# deflection_amplifier.net
KiCad netlist of a schematic drawn in EAGLE
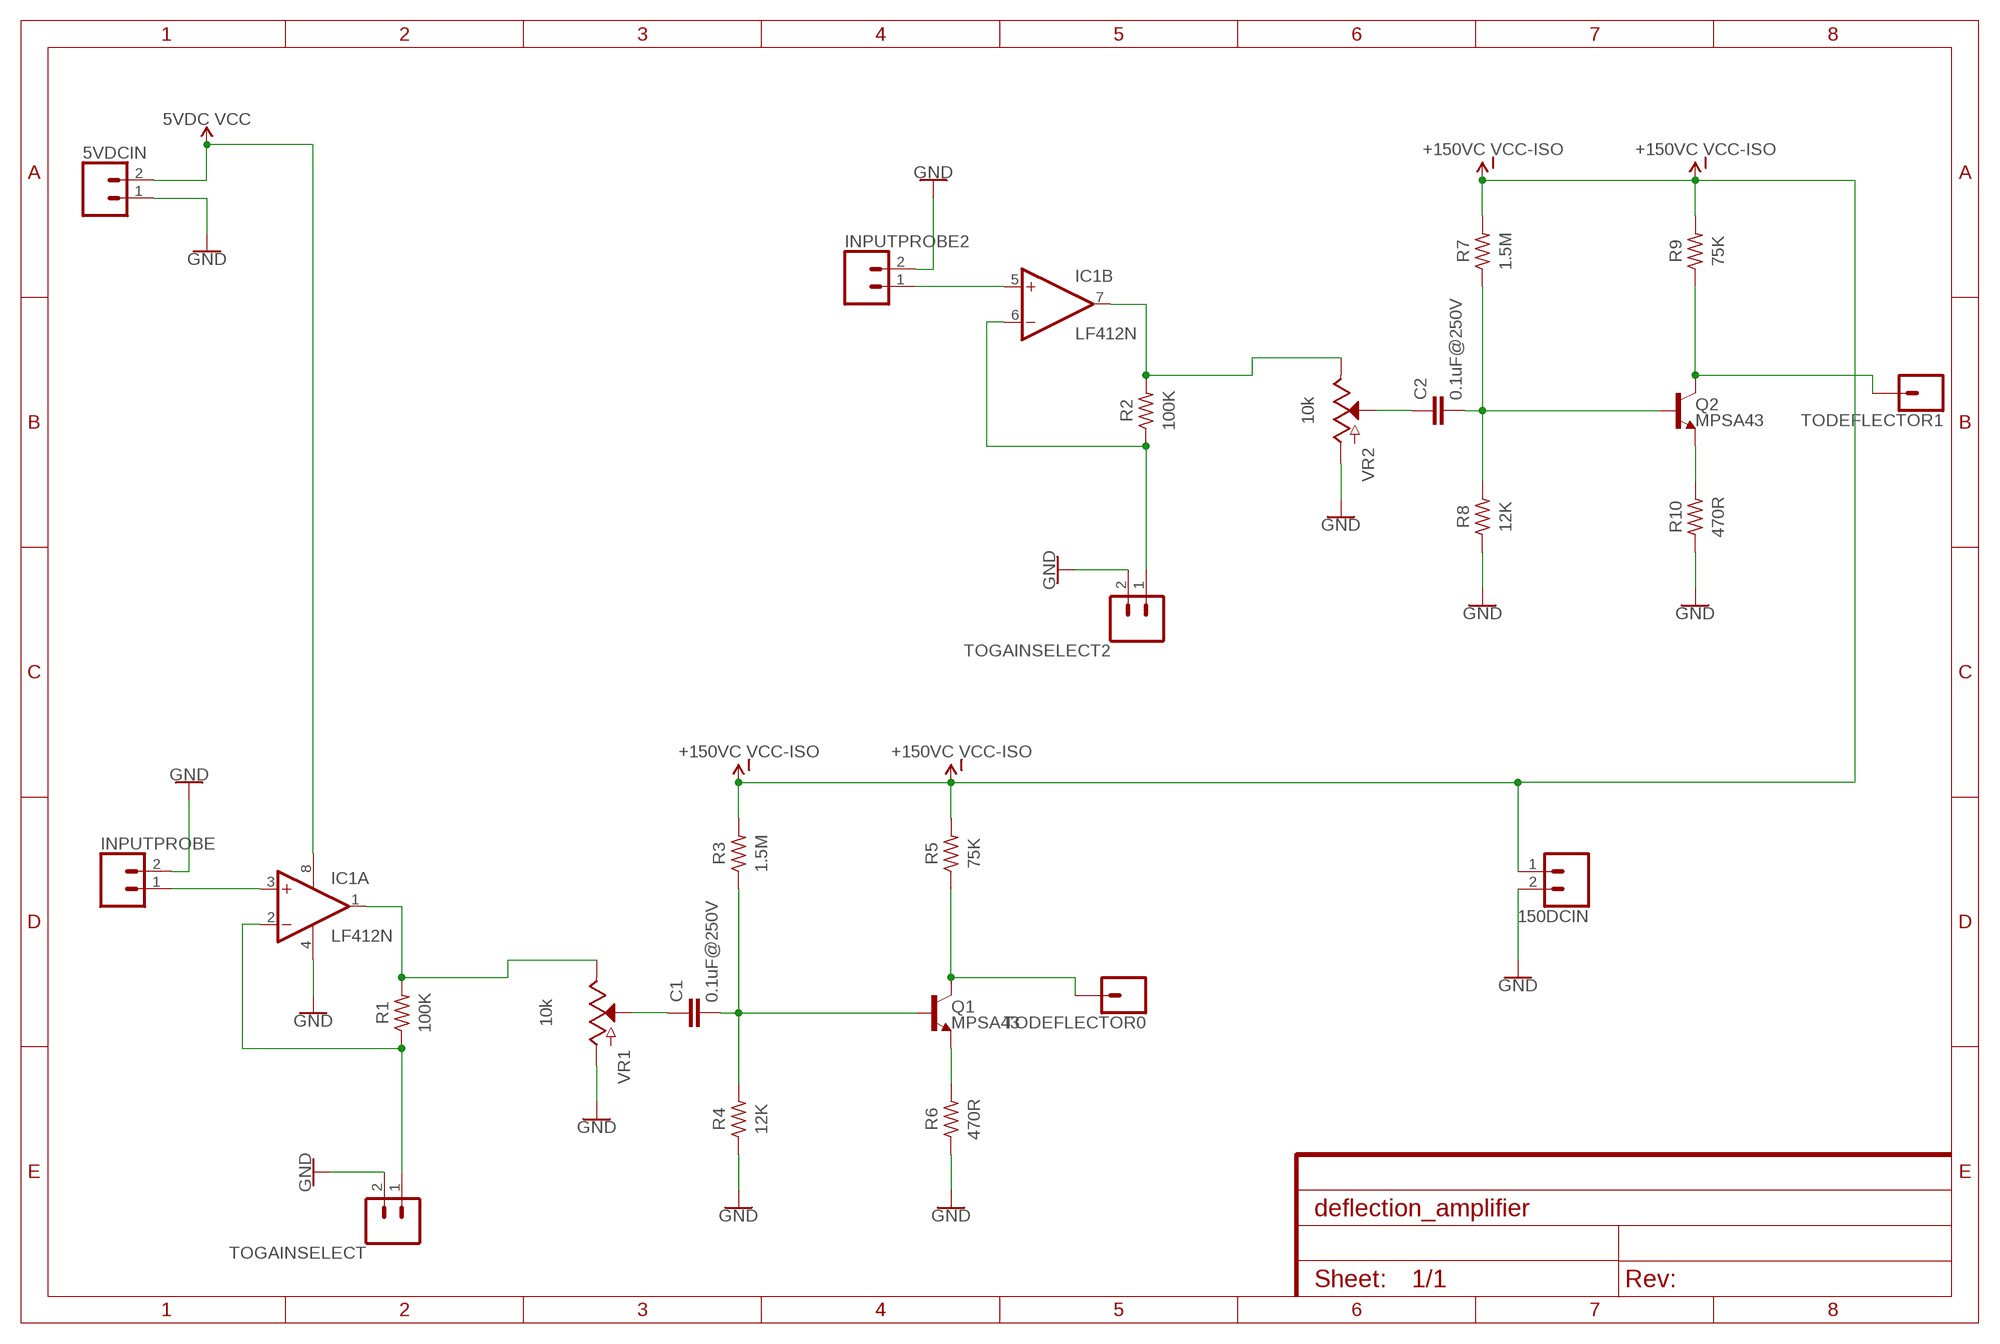
[diagram p0: schematic, sheet 1]

(export (version "E")
  (design (tool "Eeschema 10.0.6"))
  (components
    (comp (ref "5VDCIN")
      (value "CONN_02")
      (footprint "eagle-import:1X02")
      (libsource (lib "eagle-import") (part "CONN_02"))
    )
    (comp (ref "150DCIN")
      (value "CONN_02")
      (footprint "eagle-import:1X02")
      (libsource (lib "eagle-import") (part "CONN_02"))
    )
    (comp (ref "C1")
      (value "0.1uF@250V")
      (footprint "eagle-import:C15B8")
      (libsource (lib "eagle-import") (part "C15/8"))
    )
    (comp (ref "C2")
      (value "0.1uF@250V")
      (footprint "eagle-import:C15B8")
      (libsource (lib "eagle-import") (part "C15/8"))
    )
    (comp (ref "IC1")
      (value "LF412N")
      (footprint "eagle-import:DIL08")
      (libsource (lib "eagle-import") (part "LF412N"))
    )
    (comp (ref "INPUTPROBE")
      (value "CONN_02")
      (footprint "eagle-import:1X02")
      (libsource (lib "eagle-import") (part "CONN_02"))
    )
    (comp (ref "INPUTPROBE2")
      (value "CONN_02")
      (footprint "eagle-import:1X02")
      (libsource (lib "eagle-import") (part "CONN_02"))
    )
    (comp (ref "Q1")
      (value "MPSA43")
      (footprint "eagle-import:TO-92")
      (libsource (lib "eagle-import") (part "TRANS_NPN-2N3904"))
    )
    (comp (ref "Q2")
      (value "MPSA43")
      (footprint "eagle-import:TO-92")
      (libsource (lib "eagle-import") (part "TRANS_NPN-2N3904"))
    )
    (comp (ref "R1")
      (value "100K")
      (footprint "eagle-import:RESAD1176W63L850D250B")
      (libsource (lib "eagle-import") (part "R-USAXIAL-11.7MM-PITCH_"))
    )
    (comp (ref "R2")
      (value "100K")
      (footprint "eagle-import:RESAD1176W63L850D250B")
      (libsource (lib "eagle-import") (part "R-USAXIAL-11.7MM-PITCH_"))
    )
    (comp (ref "R3")
      (value "1.5M")
      (footprint "eagle-import:RESAD1176W63L850D250B")
      (libsource (lib "eagle-import") (part "R-USAXIAL-11.7MM-PITCH_"))
    )
    (comp (ref "R4")
      (value "12K")
      (footprint "eagle-import:RESAD1176W63L850D250B")
      (libsource (lib "eagle-import") (part "R-USAXIAL-11.7MM-PITCH_"))
    )
    (comp (ref "R5")
      (value "75K")
      (footprint "eagle-import:RESAD1176W63L850D250B")
      (libsource (lib "eagle-import") (part "R-USAXIAL-11.7MM-PITCH_"))
    )
    (comp (ref "R6")
      (value "470R")
      (footprint "eagle-import:RESAD1176W63L850D250B")
      (libsource (lib "eagle-import") (part "R-USAXIAL-11.7MM-PITCH_"))
    )
    (comp (ref "R7")
      (value "1.5M")
      (footprint "eagle-import:RESAD1176W63L850D250B")
      (libsource (lib "eagle-import") (part "R-USAXIAL-11.7MM-PITCH_"))
    )
    (comp (ref "R8")
      (value "12K")
      (footprint "eagle-import:RESAD1176W63L850D250B")
      (libsource (lib "eagle-import") (part "R-USAXIAL-11.7MM-PITCH_"))
    )
    (comp (ref "R9")
      (value "75K")
      (footprint "eagle-import:RESAD1176W63L850D250B")
      (libsource (lib "eagle-import") (part "R-USAXIAL-11.7MM-PITCH_"))
    )
    (comp (ref "R10")
      (value "470R")
      (footprint "eagle-import:RESAD1176W63L850D250B")
      (libsource (lib "eagle-import") (part "R-USAXIAL-11.7MM-PITCH_"))
    )
    (comp (ref "TODEFLECTOR0")
      (value "CONN_01")
      (footprint "eagle-import:1X01")
      (libsource (lib "eagle-import") (part "CONN_01"))
    )
    (comp (ref "TODEFLECTOR1")
      (value "CONN_01")
      (footprint "eagle-import:1X01")
      (libsource (lib "eagle-import") (part "CONN_01"))
    )
    (comp (ref "TOGAINSELECT")
      (value "CONN_02")
      (footprint "eagle-import:1X02")
      (libsource (lib "eagle-import") (part "CONN_02"))
    )
    (comp (ref "TOGAINSELECT2")
      (value "CONN_02")
      (footprint "eagle-import:1X02")
      (libsource (lib "eagle-import") (part "CONN_02"))
    )
    (comp (ref "VR1")
      (value "10k")
      (footprint "eagle-import:POT-PTH-ALPS")
      (libsource (lib "eagle-import") (part "POTENTIOMETER-PTH-9MM-1/20W-20%"))
    )
    (comp (ref "VR2")
      (value "10k")
      (footprint "eagle-import:POT-PTH-ALPS")
      (libsource (lib "eagle-import") (part "POTENTIOMETER-PTH-9MM-1/20W-20%"))
    )
  )
  (nets
    (net (code "1") (name "+150VC VCC-ISO") (class "Default")
      (node (ref "150DCIN") (pin "1") (pinfunction "1_1") (pintype "passive"))
      (node (ref "R3") (pin "2") (pinfunction "2_2") (pintype "passive"))
      (node (ref "R5") (pin "2") (pinfunction "2_2") (pintype "passive"))
      (node (ref "R7") (pin "2") (pinfunction "2_2") (pintype "passive"))
      (node (ref "R9") (pin "2") (pinfunction "2_2") (pintype "passive"))
    )
    (net (code "2") (name "5VDC VCC") (class "Default")
      (node (ref "5VDCIN") (pin "2") (pinfunction "2_2") (pintype "passive"))
      (node (ref "IC1") (pin "8") (pinfunction "V+_8") (pintype "power_in"))
    )
    (net (code "3") (name "GND") (class "Default")
      (node (ref "150DCIN") (pin "2") (pinfunction "2_2") (pintype "passive"))
      (node (ref "5VDCIN") (pin "1") (pinfunction "1_1") (pintype "passive"))
      (node (ref "IC1") (pin "4") (pinfunction "V-_4") (pintype "power_in"))
      (node (ref "INPUTPROBE") (pin "2") (pinfunction "2_2") (pintype "passive"))
      (node (ref "INPUTPROBE2") (pin "2") (pinfunction "2_2") (pintype "passive"))
      (node (ref "R10") (pin "1") (pinfunction "1_1") (pintype "passive"))
      (node (ref "R4") (pin "1") (pinfunction "1_1") (pintype "passive"))
      (node (ref "R6") (pin "1") (pinfunction "1_1") (pintype "passive"))
      (node (ref "R8") (pin "1") (pinfunction "1_1") (pintype "passive"))
      (node (ref "TOGAINSELECT") (pin "2") (pinfunction "2_2") (pintype "passive"))
      (node (ref "TOGAINSELECT2") (pin "2") (pinfunction "2_2") (pintype "passive"))
      (node (ref "VR1") (pin "P$3") (pinfunction "A_P$3") (pintype "passive"))
      (node (ref "VR2") (pin "P$3") (pinfunction "A_P$3") (pintype "passive"))
    )
    (net (code "4") (name "Net-(IC1A-+IN)") (class "Default")
      (node (ref "IC1") (pin "3") (pinfunction "+IN_3") (pintype "input"))
      (node (ref "INPUTPROBE") (pin "1") (pinfunction "1_1") (pintype "passive"))
    )
    (net (code "5") (name "Net-(IC1A--IN)") (class "Default")
      (node (ref "IC1") (pin "2") (pinfunction "-IN_2") (pintype "input"))
      (node (ref "R1") (pin "1") (pinfunction "1_1") (pintype "passive"))
      (node (ref "TOGAINSELECT") (pin "1") (pinfunction "1_1") (pintype "passive"))
    )
    (net (code "6") (name "Net-(IC1A-OUT)") (class "Default")
      (node (ref "IC1") (pin "1") (pinfunction "OUT_1") (pintype "output"))
      (node (ref "R1") (pin "2") (pinfunction "2_2") (pintype "passive"))
      (node (ref "VR1") (pin "P$1") (pinfunction "E_P$1") (pintype "passive"))
    )
    (net (code "7") (name "Net-(IC1B-+IN)") (class "Default")
      (node (ref "IC1") (pin "5") (pinfunction "+IN_5") (pintype "input"))
      (node (ref "INPUTPROBE2") (pin "1") (pinfunction "1_1") (pintype "passive"))
    )
    (net (code "8") (name "Net-(IC1B--IN)") (class "Default")
      (node (ref "IC1") (pin "6") (pinfunction "-IN_6") (pintype "input"))
      (node (ref "R2") (pin "1") (pinfunction "1_1") (pintype "passive"))
      (node (ref "TOGAINSELECT2") (pin "1") (pinfunction "1_1") (pintype "passive"))
    )
    (net (code "9") (name "Net-(IC1B-OUT)") (class "Default")
      (node (ref "IC1") (pin "7") (pinfunction "OUT_7") (pintype "output"))
      (node (ref "R2") (pin "2") (pinfunction "2_2") (pintype "passive"))
      (node (ref "VR2") (pin "P$1") (pinfunction "E_P$1") (pintype "passive"))
    )
    (net (code "10") (name "Net-(Q1-B)") (class "Default")
      (node (ref "C1") (pin "2") (pinfunction "2_2") (pintype "passive"))
      (node (ref "Q1") (pin "2") (pinfunction "B_2") (pintype "passive"))
      (node (ref "R3") (pin "1") (pinfunction "1_1") (pintype "passive"))
      (node (ref "R4") (pin "2") (pinfunction "2_2") (pintype "passive"))
    )
    (net (code "11") (name "Net-(Q1-C)") (class "Default")
      (node (ref "Q1") (pin "3") (pinfunction "C_3") (pintype "passive"))
      (node (ref "R5") (pin "1") (pinfunction "1_1") (pintype "passive"))
      (node (ref "TODEFLECTOR0") (pin "1") (pinfunction "1_1") (pintype "passive"))
    )
    (net (code "12") (name "Net-(Q1-E)") (class "Default")
      (node (ref "Q1") (pin "1") (pinfunction "E_1") (pintype "passive"))
      (node (ref "R6") (pin "2") (pinfunction "2_2") (pintype "passive"))
    )
    (net (code "13") (name "Net-(Q2-B)") (class "Default")
      (node (ref "C2") (pin "2") (pinfunction "2_2") (pintype "passive"))
      (node (ref "Q2") (pin "2") (pinfunction "B_2") (pintype "passive"))
      (node (ref "R7") (pin "1") (pinfunction "1_1") (pintype "passive"))
      (node (ref "R8") (pin "2") (pinfunction "2_2") (pintype "passive"))
    )
    (net (code "14") (name "Net-(Q2-C)") (class "Default")
      (node (ref "Q2") (pin "3") (pinfunction "C_3") (pintype "passive"))
      (node (ref "R9") (pin "1") (pinfunction "1_1") (pintype "passive"))
      (node (ref "TODEFLECTOR1") (pin "1") (pinfunction "1_1") (pintype "passive"))
    )
    (net (code "15") (name "Net-(Q2-E)") (class "Default")
      (node (ref "Q2") (pin "1") (pinfunction "E_1") (pintype "passive"))
      (node (ref "R10") (pin "2") (pinfunction "2_2") (pintype "passive"))
    )
    (net (code "16") (name "Net-(VR1-S)") (class "Default")
      (node (ref "C1") (pin "1") (pinfunction "1_1") (pintype "passive"))
      (node (ref "VR1") (pin "P$2") (pinfunction "S_P$2") (pintype "passive"))
    )
    (net (code "17") (name "Net-(VR2-S)") (class "Default")
      (node (ref "C2") (pin "1") (pinfunction "1_1") (pintype "passive"))
      (node (ref "VR2") (pin "P$2") (pinfunction "S_P$2") (pintype "passive"))
    )
  )
)
